# arduino_due_v_1.net
KiCad netlist of a schematic drawn in EAGLE
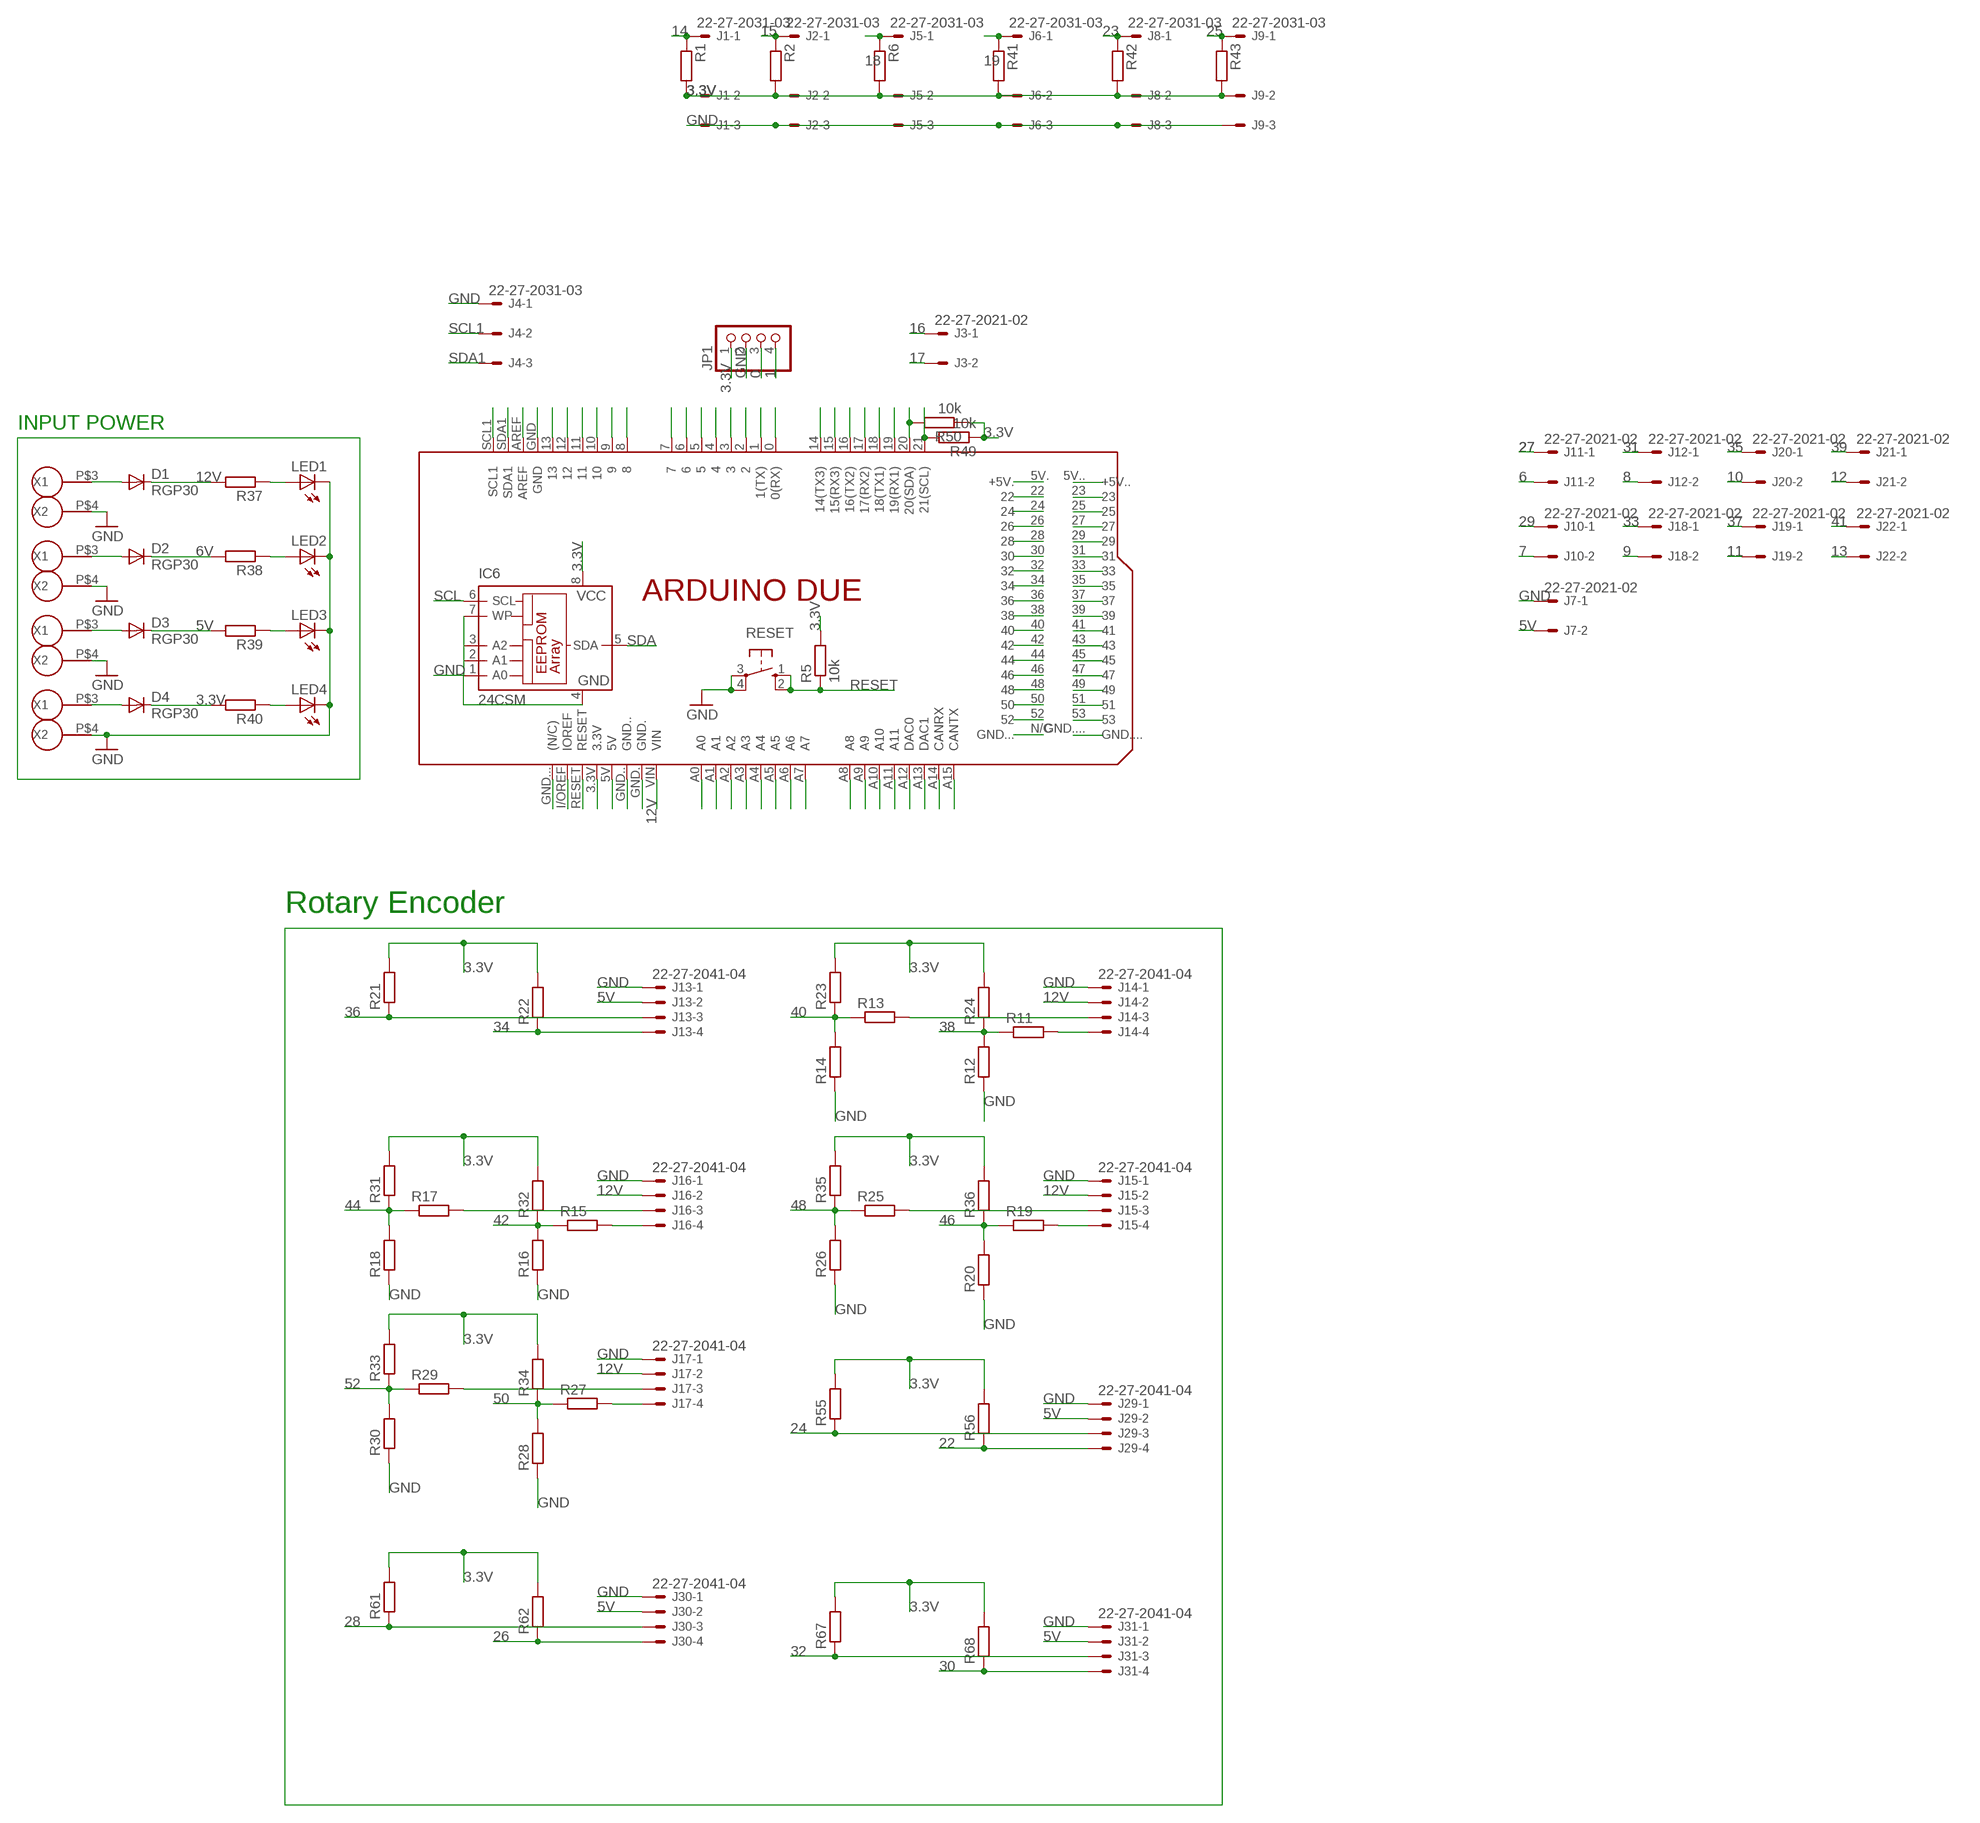
[diagram p0: schematic, sheet 1]

(export (version "E")
  (design (tool "Eeschema 10.0.6"))
  (components
    (comp (ref "D1")
      (value "RGP30")
      (footprint "eagle-import:DO201-15")
      (libsource (lib "eagle-import") (part "RGP30"))
    )
    (comp (ref "D2")
      (value "RGP30")
      (footprint "eagle-import:DO201-15")
      (libsource (lib "eagle-import") (part "RGP30"))
    )
    (comp (ref "D3")
      (value "RGP30")
      (footprint "eagle-import:DO201-15")
      (libsource (lib "eagle-import") (part "RGP30"))
    )
    (comp (ref "D4")
      (value "RGP30")
      (footprint "eagle-import:DO201-15")
      (libsource (lib "eagle-import") (part "RGP30"))
    )
    (comp (ref "IC6")
      (value "24CSM")
      (footprint "eagle-import:SO-08M")
      (fields
        (field (name "MF") "MICROCHIP")
        (field (name "MPN") "24C02C-I/SN")
        (field (name "MPN_1") "AT24C04BN-SH-B")
        (field (name "OC_FARNELL") "1362643")
        (field (name "OC_NEWARK") "50M3316")
      )
      (libsource (lib "eagle-import") (part "24CSM02C"))
    )
    (comp (ref "J1")
      (value "22-27-2031-03")
      (footprint "eagle-import:6410-03")
      (libsource (lib "eagle-import") (part "22-?-0327-2031"))
    )
    (comp (ref "J2")
      (value "22-27-2031-03")
      (footprint "eagle-import:6410-03")
      (libsource (lib "eagle-import") (part "22-?-0327-2031"))
    )
    (comp (ref "J3")
      (value "22-27-2021-02")
      (footprint "eagle-import:6410-02")
      (libsource (lib "eagle-import") (part "22-?-0227-2021"))
    )
    (comp (ref "J4")
      (value "22-27-2031-03")
      (footprint "eagle-import:6410-03")
      (libsource (lib "eagle-import") (part "22-?-0327-2031"))
    )
    (comp (ref "J5")
      (value "22-27-2031-03")
      (footprint "eagle-import:6410-03")
      (libsource (lib "eagle-import") (part "22-?-0327-2031"))
    )
    (comp (ref "J6")
      (value "22-27-2031-03")
      (footprint "eagle-import:6410-03")
      (libsource (lib "eagle-import") (part "22-?-0327-2031"))
    )
    (comp (ref "J7")
      (value "22-27-2021-02")
      (footprint "eagle-import:6410-02")
      (libsource (lib "eagle-import") (part "22-?-0227-2021"))
    )
    (comp (ref "J8")
      (value "22-27-2031-03")
      (footprint "eagle-import:6410-03")
      (libsource (lib "eagle-import") (part "22-?-0327-2031"))
    )
    (comp (ref "J9")
      (value "22-27-2031-03")
      (footprint "eagle-import:6410-03")
      (libsource (lib "eagle-import") (part "22-?-0327-2031"))
    )
    (comp (ref "J10")
      (value "22-27-2021-02")
      (footprint "eagle-import:6410-02")
      (libsource (lib "eagle-import") (part "22-?-0227-2021"))
    )
    (comp (ref "J11")
      (value "22-27-2021-02")
      (footprint "eagle-import:6410-02")
      (libsource (lib "eagle-import") (part "22-?-0227-2021"))
    )
    (comp (ref "J12")
      (value "22-27-2021-02")
      (footprint "eagle-import:6410-02")
      (libsource (lib "eagle-import") (part "22-?-0227-2021"))
    )
    (comp (ref "J13")
      (value "22-27-2041-04")
      (footprint "eagle-import:6410-04")
      (libsource (lib "eagle-import") (part "22-?-0427-2041"))
    )
    (comp (ref "J14")
      (value "22-27-2041-04")
      (footprint "eagle-import:6410-04")
      (libsource (lib "eagle-import") (part "22-?-0427-2041"))
    )
    (comp (ref "J15")
      (value "22-27-2041-04")
      (footprint "eagle-import:6410-04")
      (libsource (lib "eagle-import") (part "22-?-0427-2041"))
    )
    (comp (ref "J16")
      (value "22-27-2041-04")
      (footprint "eagle-import:6410-04")
      (libsource (lib "eagle-import") (part "22-?-0427-2041"))
    )
    (comp (ref "J17")
      (value "22-27-2041-04")
      (footprint "eagle-import:6410-04")
      (libsource (lib "eagle-import") (part "22-?-0427-2041"))
    )
    (comp (ref "J18")
      (value "22-27-2021-02")
      (footprint "eagle-import:6410-02")
      (libsource (lib "eagle-import") (part "22-?-0227-2021"))
    )
    (comp (ref "J19")
      (value "22-27-2021-02")
      (footprint "eagle-import:6410-02")
      (libsource (lib "eagle-import") (part "22-?-0227-2021"))
    )
    (comp (ref "J20")
      (value "22-27-2021-02")
      (footprint "eagle-import:6410-02")
      (libsource (lib "eagle-import") (part "22-?-0227-2021"))
    )
    (comp (ref "J21")
      (value "22-27-2021-02")
      (footprint "eagle-import:6410-02")
      (libsource (lib "eagle-import") (part "22-?-0227-2021"))
    )
    (comp (ref "J22")
      (value "22-27-2021-02")
      (footprint "eagle-import:6410-02")
      (libsource (lib "eagle-import") (part "22-?-0227-2021"))
    )
    (comp (ref "J29")
      (value "22-27-2041-04")
      (footprint "eagle-import:6410-04")
      (libsource (lib "eagle-import") (part "22-?-0427-2041"))
    )
    (comp (ref "J30")
      (value "22-27-2041-04")
      (footprint "eagle-import:6410-04")
      (libsource (lib "eagle-import") (part "22-?-0427-2041"))
    )
    (comp (ref "J31")
      (value "22-27-2041-04")
      (footprint "eagle-import:6410-04")
      (libsource (lib "eagle-import") (part "22-?-0427-2041"))
    )
    (comp (ref "JP1")
      (value "PINHD-1X4")
      (footprint "eagle-import:1X04")
      (libsource (lib "eagle-import") (part "PINHD-1X4"))
    )
    (comp (ref "LED1")
      (value "LED3MM")
      (footprint "eagle-import:LED3MM")
      (libsource (lib "eagle-import") (part "LED3MM"))
    )
    (comp (ref "LED2")
      (value "LED3MM")
      (footprint "eagle-import:LED3MM")
      (libsource (lib "eagle-import") (part "LED3MM"))
    )
    (comp (ref "LED3")
      (value "LED3MM")
      (footprint "eagle-import:LED3MM")
      (libsource (lib "eagle-import") (part "LED3MM"))
    )
    (comp (ref "LED4")
      (value "LED3MM")
      (footprint "eagle-import:LED3MM")
      (libsource (lib "eagle-import") (part "LED3MM"))
    )
    (comp (ref "PCB1")
      (value "ARDUINO_DUE")
      (footprint "eagle-import:ARDUINO_DUE")
      (libsource (lib "eagle-import") (part "ARDUINO_DUE"))
    )
    (comp (ref "R1")
      (value "R-EU_M0805")
      (footprint "eagle-import:M0805")
      (libsource (lib "eagle-import") (part "R-EU_M0805"))
    )
    (comp (ref "R2")
      (value "R-EU_M0805")
      (footprint "eagle-import:M0805")
      (libsource (lib "eagle-import") (part "R-EU_M0805"))
    )
    (comp (ref "R5")
      (value "10k")
      (footprint "eagle-import:M0805")
      (libsource (lib "eagle-import") (part "R-EU_M0805"))
    )
    (comp (ref "R6")
      (value "R-EU_M0805")
      (footprint "eagle-import:M0805")
      (libsource (lib "eagle-import") (part "R-EU_M0805"))
    )
    (comp (ref "R11")
      (value "R-EU_M0805")
      (footprint "eagle-import:M0805")
      (libsource (lib "eagle-import") (part "R-EU_M0805"))
    )
    (comp (ref "R12")
      (value "R-EU_M0805")
      (footprint "eagle-import:M0805")
      (libsource (lib "eagle-import") (part "R-EU_M0805"))
    )
    (comp (ref "R13")
      (value "R-EU_M0805")
      (footprint "eagle-import:M0805")
      (libsource (lib "eagle-import") (part "R-EU_M0805"))
    )
    (comp (ref "R14")
      (value "R-EU_M0805")
      (footprint "eagle-import:M0805")
      (libsource (lib "eagle-import") (part "R-EU_M0805"))
    )
    (comp (ref "R15")
      (value "R-EU_M0805")
      (footprint "eagle-import:M0805")
      (libsource (lib "eagle-import") (part "R-EU_M0805"))
    )
    (comp (ref "R16")
      (value "R-EU_M0805")
      (footprint "eagle-import:M0805")
      (libsource (lib "eagle-import") (part "R-EU_M0805"))
    )
    (comp (ref "R17")
      (value "R-EU_M0805")
      (footprint "eagle-import:M0805")
      (libsource (lib "eagle-import") (part "R-EU_M0805"))
    )
    (comp (ref "R18")
      (value "R-EU_M0805")
      (footprint "eagle-import:M0805")
      (libsource (lib "eagle-import") (part "R-EU_M0805"))
    )
    (comp (ref "R19")
      (value "R-EU_M0805")
      (footprint "eagle-import:M0805")
      (libsource (lib "eagle-import") (part "R-EU_M0805"))
    )
    (comp (ref "R20")
      (value "R-EU_M0805")
      (footprint "eagle-import:M0805")
      (libsource (lib "eagle-import") (part "R-EU_M0805"))
    )
    (comp (ref "R21")
      (value "R-EU_M0805")
      (footprint "eagle-import:M0805")
      (libsource (lib "eagle-import") (part "R-EU_M0805"))
    )
    (comp (ref "R22")
      (value "R-EU_M0805")
      (footprint "eagle-import:M0805")
      (libsource (lib "eagle-import") (part "R-EU_M0805"))
    )
    (comp (ref "R23")
      (value "R-EU_M0805")
      (footprint "eagle-import:M0805")
      (libsource (lib "eagle-import") (part "R-EU_M0805"))
    )
    (comp (ref "R24")
      (value "R-EU_M0805")
      (footprint "eagle-import:M0805")
      (libsource (lib "eagle-import") (part "R-EU_M0805"))
    )
    (comp (ref "R25")
      (value "R-EU_M0805")
      (footprint "eagle-import:M0805")
      (libsource (lib "eagle-import") (part "R-EU_M0805"))
    )
    (comp (ref "R26")
      (value "R-EU_M0805")
      (footprint "eagle-import:M0805")
      (libsource (lib "eagle-import") (part "R-EU_M0805"))
    )
    (comp (ref "R27")
      (value "R-EU_M0805")
      (footprint "eagle-import:M0805")
      (libsource (lib "eagle-import") (part "R-EU_M0805"))
    )
    (comp (ref "R28")
      (value "R-EU_M0805")
      (footprint "eagle-import:M0805")
      (libsource (lib "eagle-import") (part "R-EU_M0805"))
    )
    (comp (ref "R29")
      (value "R-EU_M0805")
      (footprint "eagle-import:M0805")
      (libsource (lib "eagle-import") (part "R-EU_M0805"))
    )
    (comp (ref "R30")
      (value "R-EU_M0805")
      (footprint "eagle-import:M0805")
      (libsource (lib "eagle-import") (part "R-EU_M0805"))
    )
    (comp (ref "R31")
      (value "R-EU_M0805")
      (footprint "eagle-import:M0805")
      (libsource (lib "eagle-import") (part "R-EU_M0805"))
    )
    (comp (ref "R32")
      (value "R-EU_M0805")
      (footprint "eagle-import:M0805")
      (libsource (lib "eagle-import") (part "R-EU_M0805"))
    )
    (comp (ref "R33")
      (value "R-EU_M0805")
      (footprint "eagle-import:M0805")
      (libsource (lib "eagle-import") (part "R-EU_M0805"))
    )
    (comp (ref "R34")
      (value "R-EU_M0805")
      (footprint "eagle-import:M0805")
      (libsource (lib "eagle-import") (part "R-EU_M0805"))
    )
    (comp (ref "R35")
      (value "R-EU_M0805")
      (footprint "eagle-import:M0805")
      (libsource (lib "eagle-import") (part "R-EU_M0805"))
    )
    (comp (ref "R36")
      (value "R-EU_M0805")
      (footprint "eagle-import:M0805")
      (libsource (lib "eagle-import") (part "R-EU_M0805"))
    )
    (comp (ref "R37")
      (value "R-EU_M0805")
      (footprint "eagle-import:M0805")
      (libsource (lib "eagle-import") (part "R-EU_M0805"))
    )
    (comp (ref "R38")
      (value "R-EU_M0805")
      (footprint "eagle-import:M0805")
      (libsource (lib "eagle-import") (part "R-EU_M0805"))
    )
    (comp (ref "R39")
      (value "R-EU_M0805")
      (footprint "eagle-import:M0805")
      (libsource (lib "eagle-import") (part "R-EU_M0805"))
    )
    (comp (ref "R40")
      (value "R-EU_M0805")
      (footprint "eagle-import:M0805")
      (libsource (lib "eagle-import") (part "R-EU_M0805"))
    )
    (comp (ref "R41")
      (value "R-EU_M0805")
      (footprint "eagle-import:M0805")
      (libsource (lib "eagle-import") (part "R-EU_M0805"))
    )
    (comp (ref "R42")
      (value "R-EU_M0805")
      (footprint "eagle-import:M0805")
      (libsource (lib "eagle-import") (part "R-EU_M0805"))
    )
    (comp (ref "R43")
      (value "R-EU_M0805")
      (footprint "eagle-import:M0805")
      (libsource (lib "eagle-import") (part "R-EU_M0805"))
    )
    (comp (ref "R49")
      (value "10k")
      (footprint "eagle-import:M0805")
      (libsource (lib "eagle-import") (part "R-EU_M0805"))
    )
    (comp (ref "R50")
      (value "10k")
      (footprint "eagle-import:M0805")
      (libsource (lib "eagle-import") (part "R-EU_M0805"))
    )
    (comp (ref "R55")
      (value "R-EU_M0805")
      (footprint "eagle-import:M0805")
      (libsource (lib "eagle-import") (part "R-EU_M0805"))
    )
    (comp (ref "R56")
      (value "R-EU_M0805")
      (footprint "eagle-import:M0805")
      (libsource (lib "eagle-import") (part "R-EU_M0805"))
    )
    (comp (ref "R61")
      (value "R-EU_M0805")
      (footprint "eagle-import:M0805")
      (libsource (lib "eagle-import") (part "R-EU_M0805"))
    )
    (comp (ref "R62")
      (value "R-EU_M0805")
      (footprint "eagle-import:M0805")
      (libsource (lib "eagle-import") (part "R-EU_M0805"))
    )
    (comp (ref "R67")
      (value "R-EU_M0805")
      (footprint "eagle-import:M0805")
      (libsource (lib "eagle-import") (part "R-EU_M0805"))
    )
    (comp (ref "R68")
      (value "R-EU_M0805")
      (footprint "eagle-import:M0805")
      (libsource (lib "eagle-import") (part "R-EU_M0805"))
    )
    (comp (ref "RESET")
      (value "40-XX")
      (footprint "eagle-import:B3F-40XX")
      (fields (field (name "MF") "OMRON COMPONENTS USA") (field (name "MPN") "B3F-4000"))
      (libsource (lib "eagle-import") (part "40-XX"))
    )
    (comp (ref "U$1")
      (value "TB9.5")
      (footprint "eagle-import:TB9.5")
      (libsource (lib "eagle-import") (part "TB9.5"))
    )
    (comp (ref "U$2")
      (value "TB9.5")
      (footprint "eagle-import:TB9.5")
      (libsource (lib "eagle-import") (part "TB9.5"))
    )
    (comp (ref "U$3")
      (value "TB9.5")
      (footprint "eagle-import:TB9.5")
      (libsource (lib "eagle-import") (part "TB9.5"))
    )
    (comp (ref "U$8")
      (value "TB9.5")
      (footprint "eagle-import:TB9.5")
      (libsource (lib "eagle-import") (part "TB9.5"))
    )
  )
  (nets
    (net (code "1") (name "/0") (class "Default")
      (node (ref "JP1") (pin "3") (pinfunction "3_3") (pintype "passive"))
      (node (ref "PCB1") (pin "0") (pinfunction "0(RX)_0") (pintype "bidirectional"))
    )
    (net (code "2") (name "/1") (class "Default")
      (node (ref "JP1") (pin "4") (pinfunction "4_4") (pintype "passive"))
      (node (ref "PCB1") (pin "1") (pinfunction "1(TX)_1") (pintype "bidirectional"))
    )
    (net (code "3") (name "/3.3V") (class "Default")
      (node (ref "D4") (pin "C") (pinfunction "C_C") (pintype "passive"))
      (node (ref "IC6") (pin "8") (pinfunction "VCC_8") (pintype "power_in"))
      (node (ref "J1") (pin "2") (pinfunction "S_2") (pintype "passive"))
      (node (ref "J2") (pin "2") (pinfunction "S_2") (pintype "passive"))
      (node (ref "J5") (pin "2") (pinfunction "S_2") (pintype "passive"))
      (node (ref "J6") (pin "2") (pinfunction "S_2") (pintype "passive"))
      (node (ref "J8") (pin "2") (pinfunction "S_2") (pintype "passive"))
      (node (ref "J9") (pin "2") (pinfunction "S_2") (pintype "passive"))
      (node (ref "JP1") (pin "1") (pinfunction "1_1") (pintype "passive"))
      (node (ref "R1") (pin "2") (pinfunction "2_2") (pintype "passive"))
      (node (ref "R2") (pin "2") (pinfunction "2_2") (pintype "passive"))
      (node (ref "R21") (pin "2") (pinfunction "2_2") (pintype "passive"))
      (node (ref "R22") (pin "2") (pinfunction "2_2") (pintype "passive"))
      (node (ref "R23") (pin "2") (pinfunction "2_2") (pintype "passive"))
      (node (ref "R24") (pin "2") (pinfunction "2_2") (pintype "passive"))
      (node (ref "R31") (pin "2") (pinfunction "2_2") (pintype "passive"))
      (node (ref "R32") (pin "2") (pinfunction "2_2") (pintype "passive"))
      (node (ref "R33") (pin "2") (pinfunction "2_2") (pintype "passive"))
      (node (ref "R34") (pin "2") (pinfunction "2_2") (pintype "passive"))
      (node (ref "R35") (pin "2") (pinfunction "2_2") (pintype "passive"))
      (node (ref "R36") (pin "2") (pinfunction "2_2") (pintype "passive"))
      (node (ref "R40") (pin "2") (pinfunction "2_2") (pintype "passive"))
      (node (ref "R41") (pin "2") (pinfunction "2_2") (pintype "passive"))
      (node (ref "R42") (pin "2") (pinfunction "2_2") (pintype "passive"))
      (node (ref "R43") (pin "2") (pinfunction "2_2") (pintype "passive"))
      (node (ref "R49") (pin "1") (pinfunction "1_1") (pintype "passive"))
      (node (ref "R5") (pin "2") (pinfunction "2_2") (pintype "passive"))
      (node (ref "R50") (pin "1") (pinfunction "1_1") (pintype "passive"))
      (node (ref "R55") (pin "2") (pinfunction "2_2") (pintype "passive"))
      (node (ref "R56") (pin "2") (pinfunction "2_2") (pintype "passive"))
      (node (ref "R6") (pin "2") (pinfunction "2_2") (pintype "passive"))
      (node (ref "R61") (pin "2") (pinfunction "2_2") (pintype "passive"))
      (node (ref "R62") (pin "2") (pinfunction "2_2") (pintype "passive"))
      (node (ref "R67") (pin "2") (pinfunction "2_2") (pintype "passive"))
      (node (ref "R68") (pin "2") (pinfunction "2_2") (pintype "passive"))
    )
    (net (code "4") (name "/5V") (class "Default")
      (node (ref "D3") (pin "C") (pinfunction "C_C") (pintype "passive"))
      (node (ref "J13") (pin "2") (pinfunction "S_2") (pintype "passive"))
      (node (ref "J29") (pin "2") (pinfunction "S_2") (pintype "passive"))
      (node (ref "J30") (pin "2") (pinfunction "S_2") (pintype "passive"))
      (node (ref "J31") (pin "2") (pinfunction "S_2") (pintype "passive"))
      (node (ref "J7") (pin "2") (pinfunction "S_2") (pintype "passive"))
      (node (ref "R39") (pin "2") (pinfunction "2_2") (pintype "passive"))
    )
    (net (code "5") (name "/6") (class "Default")
      (node (ref "J11") (pin "2") (pinfunction "S_2") (pintype "passive"))
      (node (ref "PCB1") (pin "6") (pinfunction "6_6") (pintype "bidirectional"))
    )
    (net (code "6") (name "/6V") (class "Default")
      (node (ref "D2") (pin "C") (pinfunction "C_C") (pintype "passive"))
      (node (ref "R38") (pin "2") (pinfunction "2_2") (pintype "passive"))
    )
    (net (code "7") (name "/7") (class "Default")
      (node (ref "J10") (pin "2") (pinfunction "S_2") (pintype "passive"))
      (node (ref "PCB1") (pin "7") (pinfunction "7_7") (pintype "bidirectional"))
    )
    (net (code "8") (name "/8") (class "Default")
      (node (ref "J12") (pin "2") (pinfunction "S_2") (pintype "passive"))
      (node (ref "PCB1") (pin "8") (pinfunction "8_8") (pintype "bidirectional"))
    )
    (net (code "9") (name "/9") (class "Default")
      (node (ref "J18") (pin "2") (pinfunction "S_2") (pintype "passive"))
      (node (ref "PCB1") (pin "9") (pinfunction "9_9") (pintype "bidirectional"))
    )
    (net (code "10") (name "/10") (class "Default")
      (node (ref "J20") (pin "2") (pinfunction "S_2") (pintype "passive"))
      (node (ref "PCB1") (pin "10") (pinfunction "10_10") (pintype "bidirectional"))
    )
    (net (code "11") (name "/11") (class "Default")
      (node (ref "J19") (pin "2") (pinfunction "S_2") (pintype "passive"))
      (node (ref "PCB1") (pin "11") (pinfunction "11_11") (pintype "bidirectional"))
    )
    (net (code "12") (name "/12") (class "Default")
      (node (ref "J21") (pin "2") (pinfunction "S_2") (pintype "passive"))
      (node (ref "PCB1") (pin "12") (pinfunction "12_12") (pintype "bidirectional"))
    )
    (net (code "13") (name "/12V") (class "Default")
      (node (ref "D1") (pin "C") (pinfunction "C_C") (pintype "passive"))
      (node (ref "J14") (pin "2") (pinfunction "S_2") (pintype "passive"))
      (node (ref "J15") (pin "2") (pinfunction "S_2") (pintype "passive"))
      (node (ref "J16") (pin "2") (pinfunction "S_2") (pintype "passive"))
      (node (ref "J17") (pin "2") (pinfunction "S_2") (pintype "passive"))
      (node (ref "PCB1") (pin "VIN") (pinfunction "VIN_VIN") (pintype "bidirectional"))
      (node (ref "R37") (pin "2") (pinfunction "2_2") (pintype "passive"))
    )
    (net (code "14") (name "/13") (class "Default")
      (node (ref "J22") (pin "2") (pinfunction "S_2") (pintype "passive"))
      (node (ref "PCB1") (pin "13") (pinfunction "13_13") (pintype "bidirectional"))
    )
    (net (code "15") (name "/14") (class "Default")
      (node (ref "J1") (pin "1") (pinfunction "S_1") (pintype "passive"))
      (node (ref "PCB1") (pin "14") (pinfunction "14(TX3)_14") (pintype "bidirectional"))
      (node (ref "R1") (pin "1") (pinfunction "1_1") (pintype "passive"))
    )
    (net (code "16") (name "/15") (class "Default")
      (node (ref "J2") (pin "1") (pinfunction "S_1") (pintype "passive"))
      (node (ref "PCB1") (pin "15") (pinfunction "15(RX3)_15") (pintype "bidirectional"))
      (node (ref "R2") (pin "1") (pinfunction "1_1") (pintype "passive"))
    )
    (net (code "17") (name "/16") (class "Default")
      (node (ref "J3") (pin "1") (pinfunction "S_1") (pintype "passive"))
      (node (ref "PCB1") (pin "16") (pinfunction "16(TX2)_16") (pintype "bidirectional"))
    )
    (net (code "18") (name "/17") (class "Default")
      (node (ref "J3") (pin "2") (pinfunction "S_2") (pintype "passive"))
      (node (ref "PCB1") (pin "17") (pinfunction "17(RX2)_17") (pintype "bidirectional"))
    )
    (net (code "19") (name "/18") (class "Default")
      (node (ref "J5") (pin "1") (pinfunction "S_1") (pintype "passive"))
      (node (ref "PCB1") (pin "18") (pinfunction "18(TX1)_18") (pintype "bidirectional"))
      (node (ref "R6") (pin "1") (pinfunction "1_1") (pintype "passive"))
    )
    (net (code "20") (name "/19") (class "Default")
      (node (ref "J6") (pin "1") (pinfunction "S_1") (pintype "passive"))
      (node (ref "PCB1") (pin "19") (pinfunction "19(RX1)_19") (pintype "bidirectional"))
      (node (ref "R41") (pin "1") (pinfunction "1_1") (pintype "passive"))
    )
    (net (code "21") (name "/22") (class "Default")
      (node (ref "J29") (pin "4") (pinfunction "S_4") (pintype "passive"))
      (node (ref "PCB1") (pin "22") (pinfunction "22_22") (pintype "bidirectional"))
      (node (ref "R56") (pin "1") (pinfunction "1_1") (pintype "passive"))
    )
    (net (code "22") (name "/23") (class "Default")
      (node (ref "J8") (pin "1") (pinfunction "S_1") (pintype "passive"))
      (node (ref "PCB1") (pin "23") (pinfunction "23_23") (pintype "bidirectional"))
      (node (ref "R42") (pin "1") (pinfunction "1_1") (pintype "passive"))
    )
    (net (code "23") (name "/24") (class "Default")
      (node (ref "J29") (pin "3") (pinfunction "S_3") (pintype "passive"))
      (node (ref "PCB1") (pin "24") (pinfunction "24_24") (pintype "bidirectional"))
      (node (ref "R55") (pin "1") (pinfunction "1_1") (pintype "passive"))
    )
    (net (code "24") (name "/25") (class "Default")
      (node (ref "J9") (pin "1") (pinfunction "S_1") (pintype "passive"))
      (node (ref "PCB1") (pin "25") (pinfunction "25_25") (pintype "bidirectional"))
      (node (ref "R43") (pin "1") (pinfunction "1_1") (pintype "passive"))
    )
    (net (code "25") (name "/26") (class "Default")
      (node (ref "J30") (pin "4") (pinfunction "S_4") (pintype "passive"))
      (node (ref "PCB1") (pin "26") (pinfunction "26_26") (pintype "bidirectional"))
      (node (ref "R62") (pin "1") (pinfunction "1_1") (pintype "passive"))
    )
    (net (code "26") (name "/27") (class "Default")
      (node (ref "J11") (pin "1") (pinfunction "S_1") (pintype "passive"))
      (node (ref "PCB1") (pin "27") (pinfunction "27_27") (pintype "bidirectional"))
    )
    (net (code "27") (name "/28") (class "Default")
      (node (ref "J30") (pin "3") (pinfunction "S_3") (pintype "passive"))
      (node (ref "PCB1") (pin "28") (pinfunction "28_28") (pintype "bidirectional"))
      (node (ref "R61") (pin "1") (pinfunction "1_1") (pintype "passive"))
    )
    (net (code "28") (name "/29") (class "Default")
      (node (ref "J10") (pin "1") (pinfunction "S_1") (pintype "passive"))
      (node (ref "PCB1") (pin "29") (pinfunction "29_29") (pintype "bidirectional"))
    )
    (net (code "29") (name "/30") (class "Default")
      (node (ref "J31") (pin "4") (pinfunction "S_4") (pintype "passive"))
      (node (ref "PCB1") (pin "30") (pinfunction "30_30") (pintype "bidirectional"))
      (node (ref "R68") (pin "1") (pinfunction "1_1") (pintype "passive"))
    )
    (net (code "30") (name "/31") (class "Default")
      (node (ref "J12") (pin "1") (pinfunction "S_1") (pintype "passive"))
      (node (ref "PCB1") (pin "31") (pinfunction "31_31") (pintype "bidirectional"))
    )
    (net (code "31") (name "/32") (class "Default")
      (node (ref "J31") (pin "3") (pinfunction "S_3") (pintype "passive"))
      (node (ref "PCB1") (pin "32") (pinfunction "32_32") (pintype "bidirectional"))
      (node (ref "R67") (pin "1") (pinfunction "1_1") (pintype "passive"))
    )
    (net (code "32") (name "/33") (class "Default")
      (node (ref "J18") (pin "1") (pinfunction "S_1") (pintype "passive"))
      (node (ref "PCB1") (pin "33") (pinfunction "33_33") (pintype "bidirectional"))
    )
    (net (code "33") (name "/34") (class "Default")
      (node (ref "J13") (pin "4") (pinfunction "S_4") (pintype "passive"))
      (node (ref "PCB1") (pin "34") (pinfunction "34_34") (pintype "bidirectional"))
      (node (ref "R22") (pin "1") (pinfunction "1_1") (pintype "passive"))
    )
    (net (code "34") (name "/35") (class "Default")
      (node (ref "J20") (pin "1") (pinfunction "S_1") (pintype "passive"))
      (node (ref "PCB1") (pin "35") (pinfunction "35_35") (pintype "bidirectional"))
    )
    (net (code "35") (name "/36") (class "Default")
      (node (ref "J13") (pin "3") (pinfunction "S_3") (pintype "passive"))
      (node (ref "PCB1") (pin "36") (pinfunction "36_36") (pintype "bidirectional"))
      (node (ref "R21") (pin "1") (pinfunction "1_1") (pintype "passive"))
    )
    (net (code "36") (name "/37") (class "Default")
      (node (ref "J19") (pin "1") (pinfunction "S_1") (pintype "passive"))
      (node (ref "PCB1") (pin "37") (pinfunction "37_37") (pintype "bidirectional"))
    )
    (net (code "37") (name "/38") (class "Default")
      (node (ref "PCB1") (pin "38") (pinfunction "38_38") (pintype "bidirectional"))
      (node (ref "R11") (pin "1") (pinfunction "1_1") (pintype "passive"))
      (node (ref "R12") (pin "2") (pinfunction "2_2") (pintype "passive"))
      (node (ref "R24") (pin "1") (pinfunction "1_1") (pintype "passive"))
    )
    (net (code "38") (name "/39") (class "Default")
      (node (ref "J21") (pin "1") (pinfunction "S_1") (pintype "passive"))
      (node (ref "PCB1") (pin "39") (pinfunction "39_39") (pintype "bidirectional"))
    )
    (net (code "39") (name "/40") (class "Default")
      (node (ref "PCB1") (pin "40") (pinfunction "40_40") (pintype "bidirectional"))
      (node (ref "R13") (pin "1") (pinfunction "1_1") (pintype "passive"))
      (node (ref "R14") (pin "2") (pinfunction "2_2") (pintype "passive"))
      (node (ref "R23") (pin "1") (pinfunction "1_1") (pintype "passive"))
    )
    (net (code "40") (name "/41") (class "Default")
      (node (ref "J22") (pin "1") (pinfunction "S_1") (pintype "passive"))
      (node (ref "PCB1") (pin "41") (pinfunction "41_41") (pintype "bidirectional"))
    )
    (net (code "41") (name "/42") (class "Default")
      (node (ref "PCB1") (pin "42") (pinfunction "42_42") (pintype "bidirectional"))
      (node (ref "R15") (pin "1") (pinfunction "1_1") (pintype "passive"))
      (node (ref "R16") (pin "2") (pinfunction "2_2") (pintype "passive"))
      (node (ref "R32") (pin "1") (pinfunction "1_1") (pintype "passive"))
    )
    (net (code "42") (name "/44") (class "Default")
      (node (ref "PCB1") (pin "44") (pinfunction "44_44") (pintype "bidirectional"))
      (node (ref "R17") (pin "1") (pinfunction "1_1") (pintype "passive"))
      (node (ref "R18") (pin "2") (pinfunction "2_2") (pintype "passive"))
      (node (ref "R31") (pin "1") (pinfunction "1_1") (pintype "passive"))
    )
    (net (code "43") (name "/46") (class "Default")
      (node (ref "PCB1") (pin "46") (pinfunction "46_46") (pintype "bidirectional"))
      (node (ref "R19") (pin "1") (pinfunction "1_1") (pintype "passive"))
      (node (ref "R20") (pin "2") (pinfunction "2_2") (pintype "passive"))
      (node (ref "R36") (pin "1") (pinfunction "1_1") (pintype "passive"))
    )
    (net (code "44") (name "/48") (class "Default")
      (node (ref "PCB1") (pin "48") (pinfunction "48_48") (pintype "bidirectional"))
      (node (ref "R25") (pin "1") (pinfunction "1_1") (pintype "passive"))
      (node (ref "R26") (pin "2") (pinfunction "2_2") (pintype "passive"))
      (node (ref "R35") (pin "1") (pinfunction "1_1") (pintype "passive"))
    )
    (net (code "45") (name "/50") (class "Default")
      (node (ref "PCB1") (pin "50") (pinfunction "50_50") (pintype "bidirectional"))
      (node (ref "R27") (pin "1") (pinfunction "1_1") (pintype "passive"))
      (node (ref "R28") (pin "2") (pinfunction "2_2") (pintype "passive"))
      (node (ref "R34") (pin "1") (pinfunction "1_1") (pintype "passive"))
    )
    (net (code "46") (name "/52") (class "Default")
      (node (ref "PCB1") (pin "52") (pinfunction "52_52") (pintype "bidirectional"))
      (node (ref "R29") (pin "1") (pinfunction "1_1") (pintype "passive"))
      (node (ref "R30") (pin "2") (pinfunction "2_2") (pintype "passive"))
      (node (ref "R33") (pin "1") (pinfunction "1_1") (pintype "passive"))
    )
    (net (code "47") (name "/RESET") (class "Default")
      (node (ref "PCB1") (pin "RESET") (pinfunction "RESET_RESET") (pintype "bidirectional"))
      (node (ref "R5") (pin "1") (pinfunction "1_1") (pintype "passive"))
      (node (ref "RESET") (pin "1") (pinfunction "S_1") (pintype "passive"))
      (node (ref "RESET") (pin "2") (pinfunction "S1_2") (pintype "passive"))
    )
    (net (code "48") (name "/SCL") (class "Default")
      (node (ref "IC6") (pin "6") (pinfunction "SCL_6") (pintype "input"))
      (node (ref "PCB1") (pin "21") (pinfunction "21(SCL)_21") (pintype "bidirectional"))
      (node (ref "R49") (pin "2") (pinfunction "2_2") (pintype "passive"))
    )
    (net (code "49") (name "/SCL1") (class "Default")
      (node (ref "J4") (pin "2") (pinfunction "S_2") (pintype "passive"))
      (node (ref "PCB1") (pin "SCL1") (pinfunction "SCL1_SCL1") (pintype "bidirectional"))
    )
    (net (code "50") (name "/SDA") (class "Default")
      (node (ref "IC6") (pin "5") (pinfunction "SDA_5") (pintype "bidirectional"))
      (node (ref "PCB1") (pin "20") (pinfunction "20(SDA)_20") (pintype "bidirectional"))
      (node (ref "R50") (pin "2") (pinfunction "2_2") (pintype "passive"))
    )
    (net (code "51") (name "/SDA1") (class "Default")
      (node (ref "J4") (pin "3") (pinfunction "S_3") (pintype "passive"))
      (node (ref "PCB1") (pin "SDA1") (pinfunction "SDA1_SDA1") (pintype "bidirectional"))
    )
    (net (code "52") (name "GND") (class "Default")
      (node (ref "IC6") (pin "1") (pinfunction "A0_1") (pintype "input"))
      (node (ref "IC6") (pin "2") (pinfunction "A1_2") (pintype "input"))
      (node (ref "IC6") (pin "3") (pinfunction "A2_3") (pintype "input"))
      (node (ref "IC6") (pin "4") (pinfunction "GND_4") (pintype "power_in"))
      (node (ref "IC6") (pin "7") (pinfunction "WP_7") (pintype "input"))
      (node (ref "J1") (pin "3") (pinfunction "S_3") (pintype "passive"))
      (node (ref "J13") (pin "1") (pinfunction "S_1") (pintype "passive"))
      (node (ref "J14") (pin "1") (pinfunction "S_1") (pintype "passive"))
      (node (ref "J15") (pin "1") (pinfunction "S_1") (pintype "passive"))
      (node (ref "J16") (pin "1") (pinfunction "S_1") (pintype "passive"))
      (node (ref "J17") (pin "1") (pinfunction "S_1") (pintype "passive"))
      (node (ref "J2") (pin "3") (pinfunction "S_3") (pintype "passive"))
      (node (ref "J29") (pin "1") (pinfunction "S_1") (pintype "passive"))
      (node (ref "J30") (pin "1") (pinfunction "S_1") (pintype "passive"))
      (node (ref "J31") (pin "1") (pinfunction "S_1") (pintype "passive"))
      (node (ref "J4") (pin "1") (pinfunction "S_1") (pintype "passive"))
      (node (ref "J5") (pin "3") (pinfunction "S_3") (pintype "passive"))
      (node (ref "J6") (pin "3") (pinfunction "S_3") (pintype "passive"))
      (node (ref "J7") (pin "1") (pinfunction "S_1") (pintype "passive"))
      (node (ref "J8") (pin "3") (pinfunction "S_3") (pintype "passive"))
      (node (ref "J9") (pin "3") (pinfunction "S_3") (pintype "passive"))
      (node (ref "JP1") (pin "2") (pinfunction "2_2") (pintype "passive"))
      (node (ref "LED1") (pin "K") (pinfunction "C_K") (pintype "passive"))
      (node (ref "LED2") (pin "K") (pinfunction "C_K") (pintype "passive"))
      (node (ref "LED3") (pin "K") (pinfunction "C_K") (pintype "passive"))
      (node (ref "LED4") (pin "K") (pinfunction "C_K") (pintype "passive"))
      (node (ref "PCB1") (pin "GND") (pinfunction "GND_GND") (pintype "bidirectional"))
      (node (ref "R12") (pin "1") (pinfunction "1_1") (pintype "passive"))
      (node (ref "R14") (pin "1") (pinfunction "1_1") (pintype "passive"))
      (node (ref "R16") (pin "1") (pinfunction "1_1") (pintype "passive"))
      (node (ref "R18") (pin "1") (pinfunction "1_1") (pintype "passive"))
      (node (ref "R20") (pin "1") (pinfunction "1_1") (pintype "passive"))
      (node (ref "R26") (pin "1") (pinfunction "1_1") (pintype "passive"))
      (node (ref "R28") (pin "1") (pinfunction "1_1") (pintype "passive"))
      (node (ref "R30") (pin "1") (pinfunction "1_1") (pintype "passive"))
      (node (ref "RESET") (pin "3") (pinfunction "P_3") (pintype "passive"))
      (node (ref "RESET") (pin "4") (pinfunction "P1_4") (pintype "passive"))
      (node (ref "U$1") (pin "P$4") (pinfunction "X2_P$4") (pintype "output"))
      (node (ref "U$2") (pin "P$4") (pinfunction "X2_P$4") (pintype "output"))
      (node (ref "U$3") (pin "P$4") (pinfunction "X2_P$4") (pintype "output"))
      (node (ref "U$8") (pin "P$4") (pinfunction "X2_P$4") (pintype "output"))
    )
    (net (code "53") (name "Net-(J14C-S)") (class "Default")
      (node (ref "J14") (pin "3") (pinfunction "S_3") (pintype "passive"))
      (node (ref "R13") (pin "2") (pinfunction "2_2") (pintype "passive"))
    )
    (net (code "54") (name "Net-(J14D-S)") (class "Default")
      (node (ref "J14") (pin "4") (pinfunction "S_4") (pintype "passive"))
      (node (ref "R11") (pin "2") (pinfunction "2_2") (pintype "passive"))
    )
    (net (code "55") (name "Net-(J15C-S)") (class "Default")
      (node (ref "J15") (pin "3") (pinfunction "S_3") (pintype "passive"))
      (node (ref "R25") (pin "2") (pinfunction "2_2") (pintype "passive"))
    )
    (net (code "56") (name "Net-(J15D-S)") (class "Default")
      (node (ref "J15") (pin "4") (pinfunction "S_4") (pintype "passive"))
      (node (ref "R19") (pin "2") (pinfunction "2_2") (pintype "passive"))
    )
    (net (code "57") (name "Net-(J16C-S)") (class "Default")
      (node (ref "J16") (pin "3") (pinfunction "S_3") (pintype "passive"))
      (node (ref "R17") (pin "2") (pinfunction "2_2") (pintype "passive"))
    )
    (net (code "58") (name "Net-(J16D-S)") (class "Default")
      (node (ref "J16") (pin "4") (pinfunction "S_4") (pintype "passive"))
      (node (ref "R15") (pin "2") (pinfunction "2_2") (pintype "passive"))
    )
    (net (code "59") (name "Net-(J17C-S)") (class "Default")
      (node (ref "J17") (pin "3") (pinfunction "S_3") (pintype "passive"))
      (node (ref "R29") (pin "2") (pinfunction "2_2") (pintype "passive"))
    )
    (net (code "60") (name "Net-(J17D-S)") (class "Default")
      (node (ref "J17") (pin "4") (pinfunction "S_4") (pintype "passive"))
      (node (ref "R27") (pin "2") (pinfunction "2_2") (pintype "passive"))
    )
    (net (code "61") (name "Net-(LED1-PadA)") (class "Default")
      (node (ref "LED1") (pin "A") (pinfunction "A_A") (pintype "passive"))
      (node (ref "R37") (pin "1") (pinfunction "1_1") (pintype "passive"))
    )
    (net (code "62") (name "Net-(LED2-PadA)") (class "Default")
      (node (ref "LED2") (pin "A") (pinfunction "A_A") (pintype "passive"))
      (node (ref "R38") (pin "1") (pinfunction "1_1") (pintype "passive"))
    )
    (net (code "63") (name "Net-(LED3-PadA)") (class "Default")
      (node (ref "LED3") (pin "A") (pinfunction "A_A") (pintype "passive"))
      (node (ref "R39") (pin "1") (pinfunction "1_1") (pintype "passive"))
    )
    (net (code "64") (name "Net-(LED4-PadA)") (class "Default")
      (node (ref "LED4") (pin "A") (pinfunction "A_A") (pintype "passive"))
      (node (ref "R40") (pin "1") (pinfunction "1_1") (pintype "passive"))
    )
    (net (code "65") (name "Net-(U$1-X1)") (class "Default")
      (node (ref "D2") (pin "A") (pinfunction "A_A") (pintype "passive"))
      (node (ref "U$1") (pin "P$3") (pinfunction "X1_P$3") (pintype "output"))
    )
    (net (code "66") (name "Net-(U$2-X1)") (class "Default")
      (node (ref "D3") (pin "A") (pinfunction "A_A") (pintype "passive"))
      (node (ref "U$2") (pin "P$3") (pinfunction "X1_P$3") (pintype "output"))
    )
    (net (code "67") (name "Net-(U$3-X1)") (class "Default")
      (node (ref "D4") (pin "A") (pinfunction "A_A") (pintype "passive"))
      (node (ref "U$3") (pin "P$3") (pinfunction "X1_P$3") (pintype "output"))
    )
    (net (code "68") (name "Net-(U$8-X1)") (class "Default")
      (node (ref "D1") (pin "A") (pinfunction "A_A") (pintype "passive"))
      (node (ref "U$8") (pin "P$3") (pinfunction "X1_P$3") (pintype "output"))
    )
    (net (code "69") (name "unconnected-(PCB1-(N{slash}C)-PadGND...)") (class "Default")
      (node (ref "PCB1") (pin "GND...") (pinfunction "(N/C)_GND...") (pintype "bidirectional"))
    )
    (net (code "70") (name "unconnected-(PCB1-+5V.-Pad5V.)") (class "Default")
      (node (ref "PCB1") (pin "5V.") (pinfunction "+5V._5V.") (pintype "bidirectional"))
    )
    (net (code "71") (name "unconnected-(PCB1-+5V..-Pad5V..)") (class "Default")
      (node (ref "PCB1") (pin "5V..") (pinfunction "+5V.._5V..") (pintype "bidirectional"))
    )
    (net (code "72") (name "unconnected-(PCB1-CANRX-PadA14)") (class "Default")
      (node (ref "PCB1") (pin "A14") (pinfunction "CANRX_A14") (pintype "bidirectional"))
    )
    (net (code "73") (name "unconnected-(PCB1-CANTX-PadA15)") (class "Default")
      (node (ref "PCB1") (pin "A15") (pinfunction "CANTX_A15") (pintype "bidirectional"))
    )
    (net (code "74") (name "unconnected-(PCB1-DAC0-PadA12)") (class "Default")
      (node (ref "PCB1") (pin "A12") (pinfunction "DAC0_A12") (pintype "bidirectional"))
    )
    (net (code "75") (name "unconnected-(PCB1-DAC1-PadA13)") (class "Default")
      (node (ref "PCB1") (pin "A13") (pinfunction "DAC1_A13") (pintype "bidirectional"))
    )
    (net (code "76") (name "unconnected-(PCB1-GND...-PadN{slash}C)") (class "Default")
      (node (ref "PCB1") (pin "N/C") (pinfunction "GND..._N/C") (pintype "bidirectional"))
    )
    (net (code "77") (name "unconnected-(PCB1-IOREF-PadI{slash}OREF)") (class "Default")
      (node (ref "PCB1") (pin "I/OREF") (pinfunction "IOREF_I/OREF") (pintype "bidirectional"))
    )
    (net (code "78") (name "unconnected-(PCB1-Pad2)") (class "Default")
      (node (ref "PCB1") (pin "2") (pinfunction "2_2") (pintype "bidirectional"))
    )
    (net (code "79") (name "unconnected-(PCB1-Pad3)") (class "Default")
      (node (ref "PCB1") (pin "3") (pinfunction "3_3") (pintype "bidirectional"))
    )
    (net (code "80") (name "unconnected-(PCB1-Pad3.3V)") (class "Default")
      (node (ref "PCB1") (pin "3.3V") (pinfunction "3.3V_3.3V") (pintype "bidirectional"))
    )
    (net (code "81") (name "unconnected-(PCB1-Pad4)") (class "Default")
      (node (ref "PCB1") (pin "4") (pinfunction "4_4") (pintype "bidirectional"))
    )
    (net (code "82") (name "unconnected-(PCB1-Pad5)") (class "Default")
      (node (ref "PCB1") (pin "5") (pinfunction "5_5") (pintype "bidirectional"))
    )
    (net (code "83") (name "unconnected-(PCB1-Pad5V)") (class "Default")
      (node (ref "PCB1") (pin "5V") (pinfunction "5V_5V") (pintype "bidirectional"))
    )
    (net (code "84") (name "unconnected-(PCB1-Pad43)") (class "Default")
      (node (ref "PCB1") (pin "43") (pinfunction "43_43") (pintype "bidirectional"))
    )
    (net (code "85") (name "unconnected-(PCB1-Pad45)") (class "Default")
      (node (ref "PCB1") (pin "45") (pinfunction "45_45") (pintype "bidirectional"))
    )
    (net (code "86") (name "unconnected-(PCB1-Pad47)") (class "Default")
      (node (ref "PCB1") (pin "47") (pinfunction "47_47") (pintype "bidirectional"))
    )
    (net (code "87") (name "unconnected-(PCB1-Pad49)") (class "Default")
      (node (ref "PCB1") (pin "49") (pinfunction "49_49") (pintype "bidirectional"))
    )
    (net (code "88") (name "unconnected-(PCB1-Pad51)") (class "Default")
      (node (ref "PCB1") (pin "51") (pinfunction "51_51") (pintype "bidirectional"))
    )
    (net (code "89") (name "unconnected-(PCB1-Pad53)") (class "Default")
      (node (ref "PCB1") (pin "53") (pinfunction "53_53") (pintype "bidirectional"))
    )
    (net (code "90") (name "unconnected-(PCB1-PadA0)") (class "Default")
      (node (ref "PCB1") (pin "A0") (pinfunction "A0_A0") (pintype "bidirectional"))
    )
    (net (code "91") (name "unconnected-(PCB1-PadA1)") (class "Default")
      (node (ref "PCB1") (pin "A1") (pinfunction "A1_A1") (pintype "bidirectional"))
    )
    (net (code "92") (name "unconnected-(PCB1-PadA2)") (class "Default")
      (node (ref "PCB1") (pin "A2") (pinfunction "A2_A2") (pintype "bidirectional"))
    )
    (net (code "93") (name "unconnected-(PCB1-PadA3)") (class "Default")
      (node (ref "PCB1") (pin "A3") (pinfunction "A3_A3") (pintype "bidirectional"))
    )
    (net (code "94") (name "unconnected-(PCB1-PadA4)") (class "Default")
      (node (ref "PCB1") (pin "A4") (pinfunction "A4_A4") (pintype "bidirectional"))
    )
    (net (code "95") (name "unconnected-(PCB1-PadA5)") (class "Default")
      (node (ref "PCB1") (pin "A5") (pinfunction "A5_A5") (pintype "bidirectional"))
    )
    (net (code "96") (name "unconnected-(PCB1-PadA6)") (class "Default")
      (node (ref "PCB1") (pin "A6") (pinfunction "A6_A6") (pintype "bidirectional"))
    )
    (net (code "97") (name "unconnected-(PCB1-PadA7)") (class "Default")
      (node (ref "PCB1") (pin "A7") (pinfunction "A7_A7") (pintype "bidirectional"))
    )
    (net (code "98") (name "unconnected-(PCB1-PadA8)") (class "Default")
      (node (ref "PCB1") (pin "A8") (pinfunction "A8_A8") (pintype "bidirectional"))
    )
    (net (code "99") (name "unconnected-(PCB1-PadA9)") (class "Default")
      (node (ref "PCB1") (pin "A9") (pinfunction "A9_A9") (pintype "bidirectional"))
    )
    (net (code "100") (name "unconnected-(PCB1-PadA10)") (class "Default")
      (node (ref "PCB1") (pin "A10") (pinfunction "A10_A10") (pintype "bidirectional"))
    )
    (net (code "101") (name "unconnected-(PCB1-PadA11)") (class "Default")
      (node (ref "PCB1") (pin "A11") (pinfunction "A11_A11") (pintype "bidirectional"))
    )
    (net (code "102") (name "unconnected-(PCB1-PadAREF)") (class "Default")
      (node (ref "PCB1") (pin "AREF") (pinfunction "AREF_AREF") (pintype "bidirectional"))
    )
    (net (code "103") (name "unconnected-(PCB1-PadGND.)") (class "Default")
      (node (ref "PCB1") (pin "GND.") (pinfunction "GND._GND.") (pintype "bidirectional"))
    )
    (net (code "104") (name "unconnected-(PCB1-PadGND..)") (class "Default")
      (node (ref "PCB1") (pin "GND..") (pinfunction "GND.._GND..") (pintype "bidirectional"))
    )
    (net (code "105") (name "unconnected-(PCB1-PadGND....)") (class "Default")
      (node (ref "PCB1") (pin "GND....") (pinfunction "GND...._GND....") (pintype "bidirectional"))
    )
  )
)
